# P1.net
KiCad netlist of a schematic drawn in Altium Designer
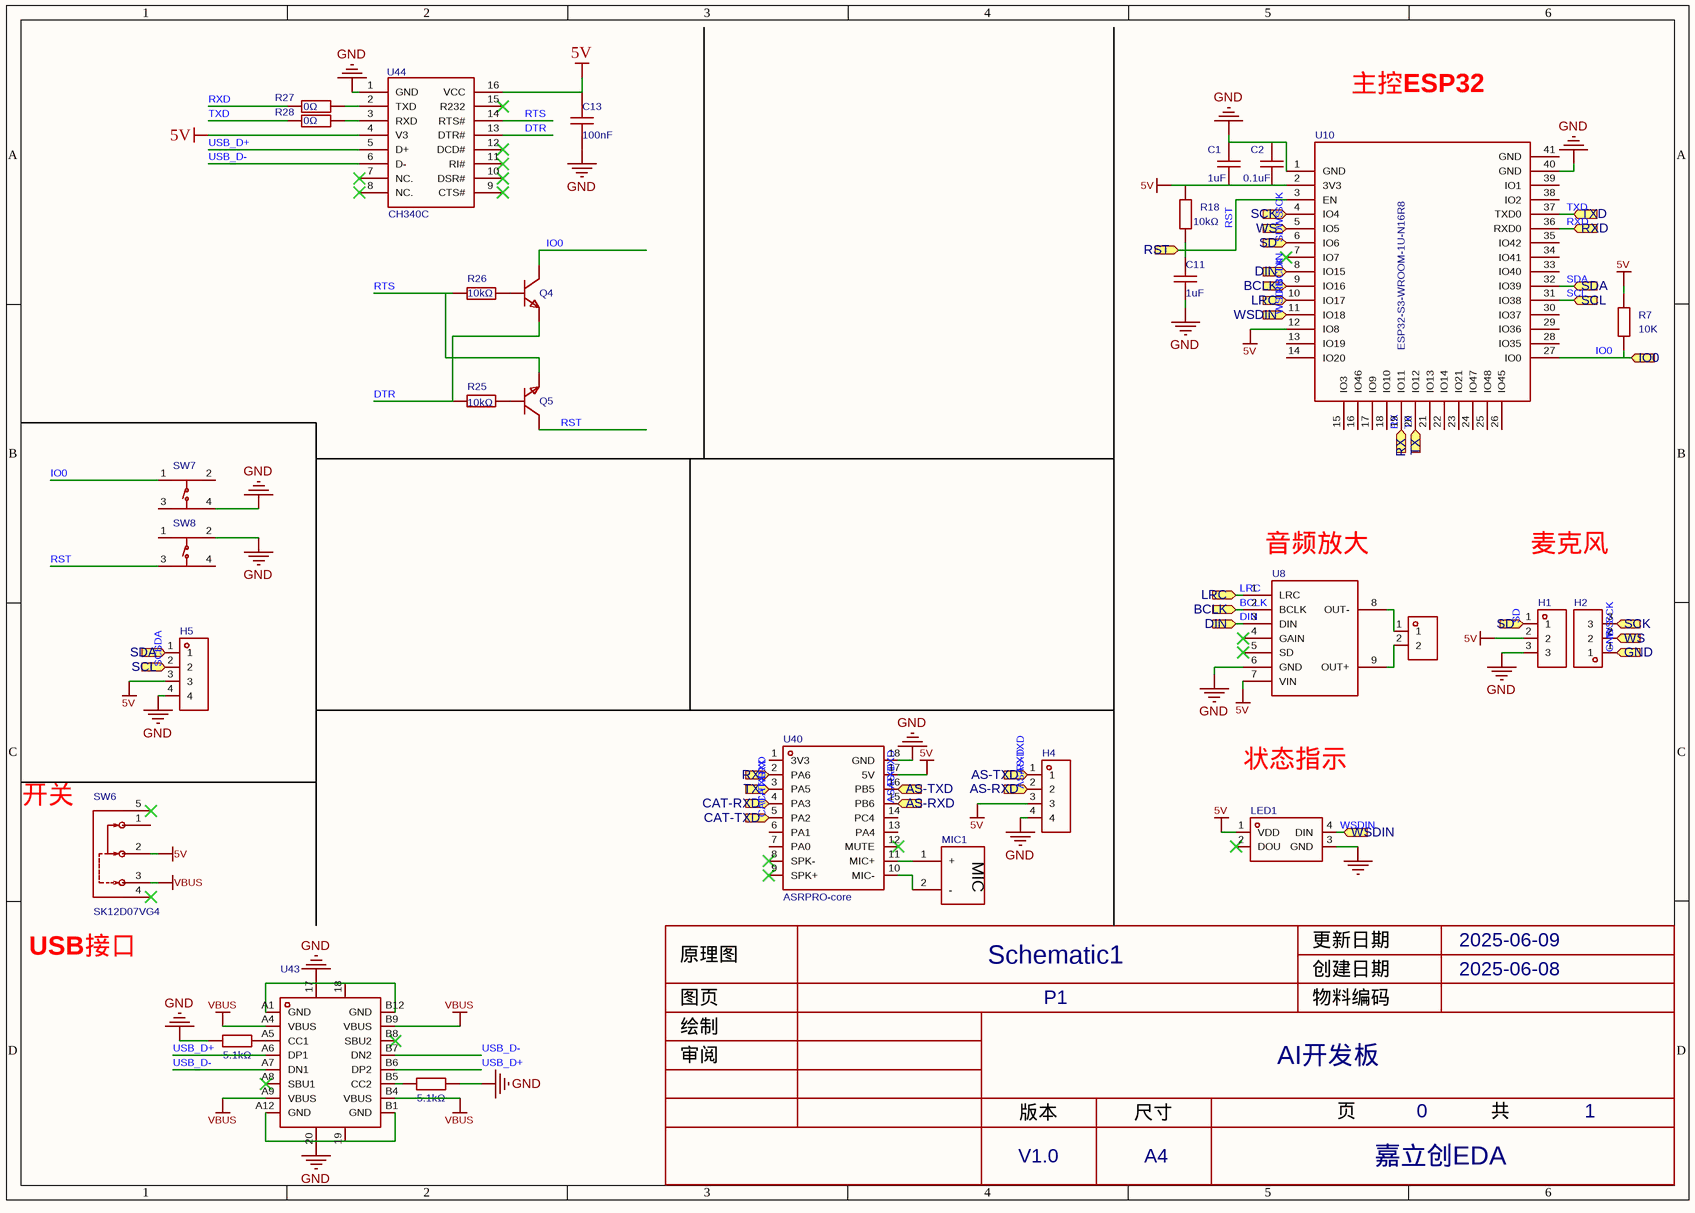
[diagram p0: P1.schdoc]

(export (version "E")
  (design (tool "Eeschema 10.0.6"))
  (components
    (comp (ref "C1")
      (value "1uF")
      (footprint "C0603")
      (description "容值:1uF;精度:±10%;额定电压:50V;材质(温度系数):X5R;")
      (fields (field (name "MANUFACTURER") "SAMSUNG(三星)") (field (name "MANUFACTURERPART") "CL10A105KB8NNNC"))
      (libsource (lib "altium-import") (part "root_1_CL10A105KB8NNNC_"))
    )
    (comp (ref "C2")
      (value "0.1uF")
      (footprint "C0603")
      (description "容值:1uF;精度:±10%;额定电压:50V;材质(温度系数):X5R;")
      (fields (field (name "MANUFACTURER") "SAMSUNG(三星)") (field (name "MANUFACTURERPART") "CL10A105KB8NNNC"))
      (libsource (lib "altium-import") (part "root_1_CL10A105KB8NNNC_"))
    )
    (comp (ref "C11")
      (value "1uF")
      (footprint "C0603")
      (description "容值:1uF;精度:±10%;额定电压:50V;材质(温度系数):X5R;")
      (fields (field (name "MANUFACTURER") "SAMSUNG(三星)") (field (name "MANUFACTURERPART") "CL10A105KB8NNNC"))
      (libsource (lib "altium-import") (part "root_1_CL10A105KB8NNNC_"))
    )
    (comp (ref "C13")
      (value "100nF")
      (footprint "C0603")
      (description "容值:100nF;精度:±10%;额定电压:50V;材质(温度系数):X7R;")
      (fields (field (name "MANUFACTURER") "YAGEO(国巨)") (field (name "MANUFACTURERPART") "CC0603KRX7R9BB104"))
      (libsource (lib "altium-import") (part "root_3_CC0603KRX7R9BB104_"))
    )
    (comp (ref "H1")
      (value "PZ254V-11-03P")
      (footprint "HDR-TH_3P-P2.54-V-M")
      (fields (field (name "MANUFACTURER") "XFCN(兴飞)"))
      (libsource (lib "altium-import") (part "root_0_PZ254V-11-03P_"))
    )
    (comp (ref "H2")
      (value "PZ254V-11-03P")
      (footprint "HDR-TH_3P-P2.54-V-M")
      (fields (field (name "MANUFACTURER") "XFCN(兴飞)"))
      (libsource (lib "altium-import") (part "root_2_PZ254V-11-03P_"))
    )
    (comp (ref "H3")
      (value "PZ254V-11-02P")
      (footprint "HDR-TH_2P-P2.54-V-M")
      (fields (field (name "MANUFACTURER") "XFCN(兴飞)"))
      (libsource (lib "altium-import") (part "root_0_PZ254V-11-02P_"))
    )
    (comp (ref "H4")
      (value "PZ254V-11-04P")
      (footprint "HDR-TH_4P-P2.54-V-M")
      (fields (field (name "MANUFACTURER") "XFCN(兴飞)"))
      (libsource (lib "altium-import") (part "root_0_PZ254V-11-04P_"))
    )
    (comp (ref "H5")
      (value "PZ254V-11-04P")
      (footprint "HDR-TH_4P-P2.54-V-M")
      (fields (field (name "MANUFACTURER") "XFCN(兴飞)"))
      (libsource (lib "altium-import") (part "root_0_PZ254V-11-04P_"))
    )
    (comp (ref "LED1")
      (value "XL-5050RGBC-WS2812B")
      (footprint "LED-SMD_4P-L5.0-W5.0-BL_XL-5050RGBC")
      (description "5050七彩幻彩透明贴片LED灯珠 5050 幻彩透明四脚 ws2812B 内置驱动IC")
      (fields (field (name "MANUFACTURER") "XINGLIGHT(成兴光)"))
      (libsource (lib "altium-import") (part "root_0_XL-5050RGBC-WS2812B_"))
    )
    (comp (ref "MIC1")
      (value "GMI6050P-36db")
      (footprint "MIC-TH_BD6.0-P1.90-D0.4-L-FD_GMI6050P-2CXXDB")
      (fields (field (name "MANUFACTURER") "INGHAi(赢海)"))
      (libsource (lib "altium-import") (part "root_3_GMI6050P-36db_"))
    )
    (comp (ref "Q4")
      (value "SS8050_C2150")
      (footprint "SOT-23-3_L2.9-W1.3-P1.90-LS2.4-BR")
      (description "晶体管类型:NPN;集电极电流(Ic):1.5A;集射极击穿电压(Vceo):25V;功率(Pd):300mW;直流电流增益(hFE@Ic,Vce):200@100mA,1V;")
      (fields (field (name "MANUFACTURER") "CJ(江苏长电/长晶)") (field (name "MANUFACTURERPART") "SS8050"))
      (libsource (lib "altium-import") (part "root_0_SS8050_C2150_"))
    )
    (comp (ref "Q5")
      (value "SS8050_C2150")
      (footprint "SOT-23-3_L2.9-W1.3-P1.90-LS2.4-BR")
      (description "晶体管类型:NPN;集电极电流(Ic):1.5A;集射极击穿电压(Vceo):25V;功率(Pd):300mW;直流电流增益(hFE@Ic,Vce):200@100mA,1V;")
      (fields (field (name "MANUFACTURER") "CJ(江苏长电/长晶)") (field (name "MANUFACTURERPART") "SS8050"))
      (libsource (lib "altium-import") (part "root_2_mirrored_SS8050_C2150_"))
    )
    (comp (ref "R6")
      (value "5.1kΩ")
      (footprint "R0603")
      (description "电阻类型:厚膜电阻;阻值:5.1kΩ;精度:±1%;功率:100mW;最大工作电压:75V;温度系数:±100ppm/℃;")
      (fields
        (field (name "MANUFACTURER PART") "0603WAF5101T5E")
        (field (name "MANUFACTURER") "UNI-ROYAL(厚声)")
      )
      (libsource (lib "altium-import") (part "root_0_0603WAF5101T5E_"))
    )
    (comp (ref "R7")
      (value "10K")
      (footprint "R0603")
      (description "电阻类型:厚膜电阻;阻值:10kΩ;精度:±1%;功率:100mW;")
      (fields
        (field (name "MANUFACTURER") "UNI-ROYAL(厚声)")
        (field (name "MANUFACTURERPART") "0603WAF1002T5E")
      )
      (libsource (lib "altium-import") (part "root_1_0603WAF1002T5E_"))
    )
    (comp (ref "R18")
      (value "10kΩ")
      (footprint "R0603")
      (description "电阻类型:厚膜电阻;阻值:10kΩ;精度:±1%;功率:100mW;")
      (fields
        (field (name "MANUFACTURER") "UNI-ROYAL(厚声)")
        (field (name "MANUFACTURERPART") "0603WAF1002T5E")
      )
      (libsource (lib "altium-import") (part "root_1_0603WAF1002T5E_"))
    )
    (comp (ref "R23")
      (value "5.1kΩ")
      (footprint "R0603")
      (description "电阻类型:厚膜电阻;阻值:5.1kΩ;精度:±1%;功率:100mW;最大工作电压:75V;温度系数:±100ppm/℃;")
      (fields
        (field (name "MANUFACTURER PART") "0603WAF5101T5E")
        (field (name "MANUFACTURER") "UNI-ROYAL(厚声)")
      )
      (libsource (lib "altium-import") (part "root_0_0603WAF5101T5E_"))
    )
    (comp (ref "R25")
      (value "10kΩ")
      (footprint "R0603")
      (description "电阻类型:厚膜电阻;阻值:10kΩ;精度:±1%;功率:100mW;最大工作电压:75V;温度系数:±100ppm/℃;")
      (fields
        (field (name "ALTIUM_VALUE") "10kΩ")
        (field (name "MANUFACTURER") "UNI-ROYAL(厚声)")
        (field (name "MANUFACTURERPART") "0603WAF1002T5E")
      )
      (libsource (lib "altium-import") (part "root_2_0603WAF1002T5E_"))
    )
    (comp (ref "R26")
      (value "10kΩ")
      (footprint "R0603")
      (description "电阻类型:厚膜电阻;阻值:10kΩ;精度:±1%;功率:100mW;最大工作电压:75V;温度系数:±100ppm/℃;")
      (fields
        (field (name "ALTIUM_VALUE") "10kΩ")
        (field (name "MANUFACTURER") "UNI-ROYAL(厚声)")
        (field (name "MANUFACTURERPART") "0603WAF1002T5E")
      )
      (libsource (lib "altium-import") (part "root_2_0603WAF1002T5E_"))
    )
    (comp (ref "R27")
      (value "0Ω")
      (footprint "R0603")
      (description "电阻类型:厚膜电阻;阻值:0Ω;精度:±1%;功率:100mW;")
      (fields
        (field (name "MANUFACTURER") "UNI-ROYAL(厚声)")
        (field (name "MANUFACTURERPART") "0603WAF0000T5E")
      )
      (libsource (lib "altium-import") (part "root_2_0603WAF0000T5E_"))
    )
    (comp (ref "R28")
      (value "0Ω")
      (footprint "R0603")
      (description "电阻类型:厚膜电阻;阻值:0Ω;精度:±1%;功率:100mW;")
      (fields
        (field (name "MANUFACTURER") "UNI-ROYAL(厚声)")
        (field (name "MANUFACTURERPART") "0603WAF0000T5E")
      )
      (libsource (lib "altium-import") (part "root_2_0603WAF0000T5E_"))
    )
    (comp (ref "SW6")
      (value "SK12D07VG4")
      (footprint "SW-TH_SK12D07VG4")
      (description "电路结构:单刀双掷;安装方式:-;额定电流(DC):500mA;额定电压(DC):50V;额定电流(AC):-;额定电压(AC):-;机械寿命:5千次;")
      (fields (field (name "MANUFACTURER") "SHOU HAN(首韩)"))
      (libsource (lib "altium-import") (part "root_3_mirrored_SK12D07VG4_"))
    )
    (comp (ref "SW7")
      (value "TS-KG89S-AT25F")
      (footprint "SW-SMD_4P-L4.2-W3.3-P2.15-LS5.1")
      (description "触点电流:50mA;额定电压(DC):12V;绝缘电阻:100MΩ;电路结构:单刀单掷;安装方式:立贴;作用力:250gf@±50gf;机械寿命:10万次;带支架:否;")
      (fields (field (name "MANUFACTURER") "HANBO(汉博)"))
      (libsource (lib "altium-import") (part "root_0_TS-KG89S-AT25F_"))
    )
    (comp (ref "SW8")
      (value "TS-KG89S-AT25F")
      (footprint "SW-SMD_4P-L4.2-W3.3-P2.15-LS5.1")
      (description "触点电流:50mA;额定电压(DC):12V;绝缘电阻:100MΩ;电路结构:单刀单掷;安装方式:立贴;作用力:250gf@±50gf;机械寿命:10万次;带支架:否;")
      (fields (field (name "MANUFACTURER") "HANBO(汉博)"))
      (libsource (lib "altium-import") (part "root_0_TS-KG89S-AT25F_"))
    )
    (comp (ref "U8")
      (value "~")
      (footprint "MAX98357moudle")
      (libsource (lib "altium-import") (part "root_3_MAX98357模块_"))
    )
    (comp (ref "U10")
      (value "ESP32-S3-WROOM-1U-N16R8")
      (footprint "WIRELM-SMD_ESP32-S3-WROOM-1U")
      (fields (field (name "MANUFACTURER") "ESPRESSIF(乐鑫)"))
      (libsource (lib "altium-import") (part "root_0_ESP32-S3-WROOM-1U-N16R8_"))
    )
    (comp (ref "U40")
      (value "ASRPRO-core")
      (footprint "COMM-SMD_ASRPRO-CORE-V1.1")
      (libsource (lib "altium-import") (part "root_0_ASRPRO-core_C9900107962_"))
    )
    (comp (ref "U43")
      (value "24018-UCAF001-A")
      (footprint "TYPE-C-USB-SMD_CF003")
      (description "TYPE C 16P母座加高1.0 H=4.25无弹")
      (fields (field (name "MANUFACTURER") "MINTRON(明硕)"))
      (libsource (lib "altium-import") (part "root_0_24018-UCAF001-A_"))
    )
    (comp (ref "U44")
      (value "CH340C")
      (footprint "SOP-16_L10.0-W3.9-P1.27-LS6.0-BL")
      (description "类型:Transceiver;协议类别:USB 2.0;驱动器/接收器数:-;数据速率:2Mbps;")
      (fields (field (name "DEVICE") "CH340C") (field (name "MANUFACTURER") "WCH(南京沁恒)"))
      (libsource (lib "altium-import") (part "root_0_CH340C_"))
    )
  )
  (nets
    (net (code "1") (name "/AS-RXD") (class "Default")
      (node (ref "H4") (pin "2") (pinfunction "2_2") (pintype "passive"))
      (node (ref "U40") (pin "15") (pinfunction "PB6_15") (pintype "passive"))
    )
    (net (code "2") (name "/AS-TXD") (class "Default")
      (node (ref "H4") (pin "1") (pinfunction "1_1") (pintype "passive"))
      (node (ref "U40") (pin "16") (pinfunction "PB5_16") (pintype "passive"))
    )
    (net (code "3") (name "/BCLK") (class "Default")
      (node (ref "U10") (pin "9") (pinfunction "IO16_9") (pintype "passive"))
      (node (ref "U8") (pin "2") (pinfunction "BCLK_2") (pintype "passive"))
    )
    (net (code "4") (name "/CAT-RXD") (class "Default")
      (node (ref "U40") (pin "4") (pinfunction "PA3_4") (pintype "passive"))
    )
    (net (code "5") (name "/CAT-TXD") (class "Default")
      (node (ref "U40") (pin "5") (pinfunction "PA2_5") (pintype "passive"))
    )
    (net (code "6") (name "/DIN") (class "Default")
      (node (ref "U10") (pin "8") (pinfunction "IO15_8") (pintype "passive"))
      (node (ref "U8") (pin "3") (pinfunction "DIN_3") (pintype "passive"))
    )
    (net (code "7") (name "/DTR") (class "Default")
      (node (ref "Q4") (pin "2") (pinfunction "E_2") (pintype "passive"))
      (node (ref "R25") (pin "2") (pinfunction "2_2") (pintype "passive"))
      (node (ref "U44") (pin "13") (pinfunction "DTR#_13") (pintype "passive"))
    )
    (net (code "8") (name "/IO0") (class "Default")
      (node (ref "Q4") (pin "3") (pinfunction "C_3") (pintype "passive"))
      (node (ref "R7") (pin "1") (pinfunction "1_1") (pintype "passive"))
      (node (ref "SW7") (pin "1") (pinfunction "1_1") (pintype "passive"))
      (node (ref "U10") (pin "27") (pinfunction "IO0_27") (pintype "passive"))
    )
    (net (code "9") (name "/LRC") (class "Default")
      (node (ref "U10") (pin "10") (pinfunction "IO17_10") (pintype "passive"))
      (node (ref "U8") (pin "1") (pinfunction "LRC_1") (pintype "passive"))
    )
    (net (code "10") (name "/RST") (class "Default")
      (node (ref "C11") (pin "2") (pinfunction "2_2") (pintype "passive"))
      (node (ref "Q5") (pin "3") (pinfunction "C_3") (pintype "passive"))
      (node (ref "R18") (pin "1") (pinfunction "1_1") (pintype "passive"))
      (node (ref "SW8") (pin "3") (pinfunction "3_3") (pintype "passive"))
      (node (ref "U10") (pin "3") (pinfunction "EN_3") (pintype "passive"))
    )
    (net (code "11") (name "/RTS") (class "Default")
      (node (ref "Q5") (pin "2") (pinfunction "E_2") (pintype "passive"))
      (node (ref "R26") (pin "2") (pinfunction "2_2") (pintype "passive"))
      (node (ref "U44") (pin "14") (pinfunction "RTS#_14") (pintype "passive"))
    )
    (net (code "12") (name "/RX") (class "Default")
      (node (ref "U10") (pin "19") (pinfunction "IO11_19") (pintype "passive"))
      (node (ref "U40") (pin "2") (pinfunction "PA6_2") (pintype "passive"))
    )
    (net (code "13") (name "/RXD") (class "Default")
      (node (ref "R27") (pin "2") (pinfunction "2_2") (pintype "passive"))
      (node (ref "U10") (pin "36") (pinfunction "RXD0_36") (pintype "passive"))
    )
    (net (code "14") (name "/SCK") (class "Default")
      (node (ref "H2") (pin "3") (pinfunction "3_3") (pintype "passive"))
      (node (ref "U10") (pin "4") (pinfunction "IO4_4") (pintype "passive"))
    )
    (net (code "15") (name "/SCL") (class "Default")
      (node (ref "H5") (pin "2") (pinfunction "2_2") (pintype "passive"))
      (node (ref "U10") (pin "31") (pinfunction "IO38_31") (pintype "passive"))
    )
    (net (code "16") (name "/SD") (class "Default")
      (node (ref "H1") (pin "1") (pinfunction "1_1") (pintype "passive"))
      (node (ref "U10") (pin "6") (pinfunction "IO6_6") (pintype "passive"))
    )
    (net (code "17") (name "/SDA") (class "Default")
      (node (ref "H5") (pin "1") (pinfunction "1_1") (pintype "passive"))
      (node (ref "U10") (pin "32") (pinfunction "IO39_32") (pintype "passive"))
    )
    (net (code "18") (name "/TX") (class "Default")
      (node (ref "U10") (pin "20") (pinfunction "IO12_20") (pintype "passive"))
      (node (ref "U40") (pin "3") (pinfunction "PA5_3") (pintype "passive"))
    )
    (net (code "19") (name "/TXD") (class "Default")
      (node (ref "R28") (pin "2") (pinfunction "2_2") (pintype "passive"))
      (node (ref "U10") (pin "37") (pinfunction "TXD0_37") (pintype "passive"))
    )
    (net (code "20") (name "/USB_D+") (class "Default")
      (node (ref "U43") (pin "A6") (pinfunction "DP1_A6") (pintype "passive"))
      (node (ref "U43") (pin "B6") (pinfunction "DP2_B6") (pintype "passive"))
      (node (ref "U44") (pin "5") (pinfunction "D+_5") (pintype "passive"))
    )
    (net (code "21") (name "/USB_D-") (class "Default")
      (node (ref "U43") (pin "A7") (pinfunction "DN1_A7") (pintype "passive"))
      (node (ref "U43") (pin "B7") (pinfunction "DN2_B7") (pintype "passive"))
      (node (ref "U44") (pin "6") (pinfunction "D-_6") (pintype "passive"))
    )
    (net (code "22") (name "/WS") (class "Default")
      (node (ref "H2") (pin "2") (pinfunction "2_2") (pintype "passive"))
      (node (ref "U10") (pin "5") (pinfunction "IO5_5") (pintype "passive"))
    )
    (net (code "23") (name "/WSDIN") (class "Default")
      (node (ref "LED1") (pin "4") (pinfunction "DIN_4") (pintype "passive"))
      (node (ref "U10") (pin "11") (pinfunction "IO18_11") (pintype "passive"))
    )
    (net (code "24") (name "5V") (class "Default")
      (node (ref "C1") (pin "1") (pinfunction "1_1") (pintype "passive"))
      (node (ref "C13") (pin "1") (pinfunction "1_1") (pintype "passive"))
      (node (ref "C2") (pin "1") (pinfunction "1_1") (pintype "passive"))
      (node (ref "H1") (pin "2") (pinfunction "2_2") (pintype "passive"))
      (node (ref "H4") (pin "3") (pinfunction "3_3") (pintype "passive"))
      (node (ref "H5") (pin "3") (pinfunction "3_3") (pintype "passive"))
      (node (ref "LED1") (pin "1") (pinfunction "VDD_1") (pintype "passive"))
      (node (ref "R18") (pin "2") (pinfunction "2_2") (pintype "passive"))
      (node (ref "R7") (pin "2") (pinfunction "2_2") (pintype "passive"))
      (node (ref "SW6") (pin "2") (pinfunction "2_2") (pintype "passive"))
      (node (ref "U10") (pin "12") (pinfunction "IO8_12") (pintype "passive"))
      (node (ref "U10") (pin "2") (pinfunction "3V3_2") (pintype "passive"))
      (node (ref "U40") (pin "17") (pinfunction "5V_17") (pintype "passive"))
      (node (ref "U44") (pin "16") (pinfunction "VCC_16") (pintype "passive"))
      (node (ref "U44") (pin "4") (pinfunction "V3_4") (pintype "passive"))
      (node (ref "U8") (pin "7") (pinfunction "VIN_7") (pintype "passive"))
    )
    (net (code "25") (name "GND") (class "Default")
      (node (ref "C1") (pin "2") (pinfunction "2_2") (pintype "passive"))
      (node (ref "C11") (pin "1") (pinfunction "1_1") (pintype "passive"))
      (node (ref "C13") (pin "2") (pinfunction "2_2") (pintype "passive"))
      (node (ref "C2") (pin "2") (pinfunction "2_2") (pintype "passive"))
      (node (ref "H1") (pin "3") (pinfunction "3_3") (pintype "passive"))
      (node (ref "H2") (pin "1") (pinfunction "1_1") (pintype "passive"))
      (node (ref "H4") (pin "4") (pinfunction "4_4") (pintype "passive"))
      (node (ref "H5") (pin "4") (pinfunction "4_4") (pintype "passive"))
      (node (ref "LED1") (pin "3") (pinfunction "GND_3") (pintype "passive"))
      (node (ref "R23") (pin "1") (pinfunction "1_1") (pintype "passive"))
      (node (ref "R6") (pin "2") (pinfunction "2_2") (pintype "passive"))
      (node (ref "SW7") (pin "4") (pinfunction "4_4") (pintype "passive"))
      (node (ref "SW8") (pin "2") (pinfunction "2_2") (pintype "passive"))
      (node (ref "U10") (pin "1") (pinfunction "GND_1") (pintype "passive"))
      (node (ref "U10") (pin "40") (pinfunction "GND_40") (pintype "passive"))
      (node (ref "U40") (pin "18") (pinfunction "GND_18") (pintype "passive"))
      (node (ref "U43") (pin "17") (pinfunction "17_17") (pintype "passive"))
      (node (ref "U43") (pin "18") (pinfunction "18_18") (pintype "passive"))
      (node (ref "U43") (pin "19") (pinfunction "19_19") (pintype "passive"))
      (node (ref "U43") (pin "20") (pinfunction "20_20") (pintype "passive"))
      (node (ref "U43") (pin "A1") (pinfunction "GND_A1") (pintype "passive"))
      (node (ref "U43") (pin "A12") (pinfunction "GND_A12") (pintype "passive"))
      (node (ref "U43") (pin "B1") (pinfunction "GND_B1") (pintype "passive"))
      (node (ref "U43") (pin "B12") (pinfunction "GND_B12") (pintype "passive"))
      (node (ref "U44") (pin "1") (pinfunction "GND_1") (pintype "passive"))
      (node (ref "U8") (pin "6") (pinfunction "GND_6") (pintype "passive"))
    )
    (net (code "26") (name "Net-(MIC1-+)") (class "Default")
      (node (ref "MIC1") (pin "1") (pinfunction "+_1") (pintype "passive"))
      (node (ref "U40") (pin "11") (pinfunction "MIC+_11") (pintype "passive"))
    )
    (net (code "27") (name "Net-(MIC1--)") (class "Default")
      (node (ref "MIC1") (pin "2") (pinfunction "-_2") (pintype "passive"))
      (node (ref "U40") (pin "10") (pinfunction "MIC-_10") (pintype "passive"))
    )
    (net (code "28") (name "Net-(Q4-B)") (class "Default")
      (node (ref "Q4") (pin "1") (pinfunction "B_1") (pintype "passive"))
      (node (ref "R26") (pin "1") (pinfunction "1_1") (pintype "passive"))
    )
    (net (code "29") (name "Net-(Q5-B)") (class "Default")
      (node (ref "Q5") (pin "1") (pinfunction "B_1") (pintype "passive"))
      (node (ref "R25") (pin "1") (pinfunction "1_1") (pintype "passive"))
    )
    (net (code "30") (name "Net-(U8-OUT+)") (class "Default")
      (node (ref "H3") (pin "2") (pinfunction "2_2") (pintype "passive"))
      (node (ref "U8") (pin "9") (pinfunction "OUT+_9") (pintype "passive"))
    )
    (net (code "31") (name "Net-(U8-OUT-)") (class "Default")
      (node (ref "H3") (pin "1") (pinfunction "1_1") (pintype "passive"))
      (node (ref "U8") (pin "8") (pinfunction "OUT-_8") (pintype "passive"))
    )
    (net (code "32") (name "Net-(U43-CC1)") (class "Default")
      (node (ref "R23") (pin "2") (pinfunction "2_2") (pintype "passive"))
      (node (ref "U43") (pin "A5") (pinfunction "CC1_A5") (pintype "passive"))
    )
    (net (code "33") (name "Net-(U43-CC2)") (class "Default")
      (node (ref "R6") (pin "1") (pinfunction "1_1") (pintype "passive"))
      (node (ref "U43") (pin "B5") (pinfunction "CC2_B5") (pintype "passive"))
    )
    (net (code "34") (name "Net-(U44-RXD)") (class "Default")
      (node (ref "R28") (pin "1") (pinfunction "1_1") (pintype "passive"))
      (node (ref "U44") (pin "3") (pinfunction "RXD_3") (pintype "passive"))
    )
    (net (code "35") (name "Net-(U44-TXD)") (class "Default")
      (node (ref "R27") (pin "1") (pinfunction "1_1") (pintype "passive"))
      (node (ref "U44") (pin "2") (pinfunction "TXD_2") (pintype "passive"))
    )
    (net (code "36") (name "VBUS") (class "Default")
      (node (ref "SW6") (pin "3") (pinfunction "3_3") (pintype "passive"))
      (node (ref "U43") (pin "A4") (pinfunction "VBUS_A4") (pintype "passive"))
      (node (ref "U43") (pin "A9") (pinfunction "VBUS_A9") (pintype "passive"))
      (node (ref "U43") (pin "B4") (pinfunction "VBUS_B4") (pintype "passive"))
      (node (ref "U43") (pin "B9") (pinfunction "VBUS_B9") (pintype "passive"))
    )
    (net (code "37") (name "unconnected-(LED1-DOU-Pad2)") (class "Default")
      (node (ref "LED1") (pin "2") (pinfunction "DOU_2") (pintype "passive+no_connect"))
    )
    (net (code "38") (name "unconnected-(SW6-Pad1)") (class "Default")
      (node (ref "SW6") (pin "1") (pinfunction "1_1") (pintype "passive"))
    )
    (net (code "39") (name "unconnected-(SW6-Pad4)") (class "Default")
      (node (ref "SW6") (pin "4") (pinfunction "4_4") (pintype "passive+no_connect"))
    )
    (net (code "40") (name "unconnected-(SW6-Pad5)") (class "Default")
      (node (ref "SW6") (pin "5") (pinfunction "5_5") (pintype "passive+no_connect"))
    )
    (net (code "41") (name "unconnected-(SW7-Pad2)") (class "Default")
      (node (ref "SW7") (pin "2") (pinfunction "2_2") (pintype "passive"))
    )
    (net (code "42") (name "unconnected-(SW7-Pad3)") (class "Default")
      (node (ref "SW7") (pin "3") (pinfunction "3_3") (pintype "passive"))
    )
    (net (code "43") (name "unconnected-(SW8-Pad1)") (class "Default")
      (node (ref "SW8") (pin "1") (pinfunction "1_1") (pintype "passive"))
    )
    (net (code "44") (name "unconnected-(SW8-Pad4)") (class "Default")
      (node (ref "SW8") (pin "4") (pinfunction "4_4") (pintype "passive"))
    )
    (net (code "45") (name "unconnected-(U8-GAIN-Pad4)") (class "Default")
      (node (ref "U8") (pin "4") (pinfunction "GAIN_4") (pintype "passive+no_connect"))
    )
    (net (code "46") (name "unconnected-(U8-SD-Pad5)") (class "Default")
      (node (ref "U8") (pin "5") (pinfunction "SD_5") (pintype "passive+no_connect"))
    )
    (net (code "47") (name "unconnected-(U10-GND-Pad41)") (class "Default")
      (node (ref "U10") (pin "41") (pinfunction "GND_41") (pintype "passive"))
    )
    (net (code "48") (name "unconnected-(U10-IO1-Pad39)") (class "Default")
      (node (ref "U10") (pin "39") (pinfunction "IO1_39") (pintype "passive"))
    )
    (net (code "49") (name "unconnected-(U10-IO2-Pad38)") (class "Default")
      (node (ref "U10") (pin "38") (pinfunction "IO2_38") (pintype "passive"))
    )
    (net (code "50") (name "unconnected-(U10-IO3-Pad15)") (class "Default")
      (node (ref "U10") (pin "15") (pinfunction "IO3_15") (pintype "passive"))
    )
    (net (code "51") (name "unconnected-(U10-IO7-Pad7)") (class "Default")
      (node (ref "U10") (pin "7") (pinfunction "IO7_7") (pintype "passive+no_connect"))
    )
    (net (code "52") (name "unconnected-(U10-IO9-Pad17)") (class "Default")
      (node (ref "U10") (pin "17") (pinfunction "IO9_17") (pintype "passive"))
    )
    (net (code "53") (name "unconnected-(U10-IO10-Pad18)") (class "Default")
      (node (ref "U10") (pin "18") (pinfunction "IO10_18") (pintype "passive"))
    )
    (net (code "54") (name "unconnected-(U10-IO13-Pad21)") (class "Default")
      (node (ref "U10") (pin "21") (pinfunction "IO13_21") (pintype "passive"))
    )
    (net (code "55") (name "unconnected-(U10-IO14-Pad22)") (class "Default")
      (node (ref "U10") (pin "22") (pinfunction "IO14_22") (pintype "passive"))
    )
    (net (code "56") (name "unconnected-(U10-IO19-Pad13)") (class "Default")
      (node (ref "U10") (pin "13") (pinfunction "IO19_13") (pintype "passive"))
    )
    (net (code "57") (name "unconnected-(U10-IO20-Pad14)") (class "Default")
      (node (ref "U10") (pin "14") (pinfunction "IO20_14") (pintype "passive"))
    )
    (net (code "58") (name "unconnected-(U10-IO21-Pad23)") (class "Default")
      (node (ref "U10") (pin "23") (pinfunction "IO21_23") (pintype "passive"))
    )
    (net (code "59") (name "unconnected-(U10-IO35-Pad28)") (class "Default")
      (node (ref "U10") (pin "28") (pinfunction "IO35_28") (pintype "passive"))
    )
    (net (code "60") (name "unconnected-(U10-IO36-Pad29)") (class "Default")
      (node (ref "U10") (pin "29") (pinfunction "IO36_29") (pintype "passive"))
    )
    (net (code "61") (name "unconnected-(U10-IO37-Pad30)") (class "Default")
      (node (ref "U10") (pin "30") (pinfunction "IO37_30") (pintype "passive"))
    )
    (net (code "62") (name "unconnected-(U10-IO40-Pad33)") (class "Default")
      (node (ref "U10") (pin "33") (pinfunction "IO40_33") (pintype "passive"))
    )
    (net (code "63") (name "unconnected-(U10-IO41-Pad34)") (class "Default")
      (node (ref "U10") (pin "34") (pinfunction "IO41_34") (pintype "passive"))
    )
    (net (code "64") (name "unconnected-(U10-IO42-Pad35)") (class "Default")
      (node (ref "U10") (pin "35") (pinfunction "IO42_35") (pintype "passive"))
    )
    (net (code "65") (name "unconnected-(U10-IO45-Pad26)") (class "Default")
      (node (ref "U10") (pin "26") (pinfunction "IO45_26") (pintype "passive"))
    )
    (net (code "66") (name "unconnected-(U10-IO46-Pad16)") (class "Default")
      (node (ref "U10") (pin "16") (pinfunction "IO46_16") (pintype "passive"))
    )
    (net (code "67") (name "unconnected-(U10-IO47-Pad24)") (class "Default")
      (node (ref "U10") (pin "24") (pinfunction "IO47_24") (pintype "passive"))
    )
    (net (code "68") (name "unconnected-(U10-IO48-Pad25)") (class "Default")
      (node (ref "U10") (pin "25") (pinfunction "IO48_25") (pintype "passive"))
    )
    (net (code "69") (name "unconnected-(U40-3V3-Pad1)") (class "Default")
      (node (ref "U40") (pin "1") (pinfunction "3V3_1") (pintype "passive"))
    )
    (net (code "70") (name "unconnected-(U40-MUTE-Pad12)") (class "Default")
      (node (ref "U40") (pin "12") (pinfunction "MUTE_12") (pintype "passive+no_connect"))
    )
    (net (code "71") (name "unconnected-(U40-PA0-Pad7)") (class "Default")
      (node (ref "U40") (pin "7") (pinfunction "PA0_7") (pintype "passive"))
    )
    (net (code "72") (name "unconnected-(U40-PA1-Pad6)") (class "Default")
      (node (ref "U40") (pin "6") (pinfunction "PA1_6") (pintype "passive"))
    )
    (net (code "73") (name "unconnected-(U40-PA4-Pad13)") (class "Default")
      (node (ref "U40") (pin "13") (pinfunction "PA4_13") (pintype "passive"))
    )
    (net (code "74") (name "unconnected-(U40-PC4-Pad14)") (class "Default")
      (node (ref "U40") (pin "14") (pinfunction "PC4_14") (pintype "passive"))
    )
    (net (code "75") (name "unconnected-(U40-SPK+-Pad9)") (class "Default")
      (node (ref "U40") (pin "9") (pinfunction "SPK+_9") (pintype "passive+no_connect"))
    )
    (net (code "76") (name "unconnected-(U40-SPK--Pad8)") (class "Default")
      (node (ref "U40") (pin "8") (pinfunction "SPK-_8") (pintype "passive+no_connect"))
    )
    (net (code "77") (name "unconnected-(U43-SBU1-PadA8)") (class "Default")
      (node (ref "U43") (pin "A8") (pinfunction "SBU1_A8") (pintype "passive+no_connect"))
    )
    (net (code "78") (name "unconnected-(U43-SBU2-PadB8)") (class "Default")
      (node (ref "U43") (pin "B8") (pinfunction "SBU2_B8") (pintype "passive+no_connect"))
    )
    (net (code "79") (name "unconnected-(U44-CTS#-Pad9)") (class "Default")
      (node (ref "U44") (pin "9") (pinfunction "CTS#_9") (pintype "passive+no_connect"))
    )
    (net (code "80") (name "unconnected-(U44-DCD#-Pad12)") (class "Default")
      (node (ref "U44") (pin "12") (pinfunction "DCD#_12") (pintype "passive+no_connect"))
    )
    (net (code "81") (name "unconnected-(U44-DSR#-Pad10)") (class "Default")
      (node (ref "U44") (pin "10") (pinfunction "DSR#_10") (pintype "passive+no_connect"))
    )
    (net (code "82") (name "unconnected-(U44-NC.-Pad7)") (class "Default")
      (node (ref "U44") (pin "7") (pinfunction "NC._7") (pintype "passive+no_connect"))
    )
    (net (code "83") (name "unconnected-(U44-NC.-Pad8)") (class "Default")
      (node (ref "U44") (pin "8") (pinfunction "NC._8") (pintype "passive+no_connect"))
    )
    (net (code "84") (name "unconnected-(U44-R232-Pad15)") (class "Default")
      (node (ref "U44") (pin "15") (pinfunction "R232_15") (pintype "passive+no_connect"))
    )
    (net (code "85") (name "unconnected-(U44-RI#-Pad11)") (class "Default")
      (node (ref "U44") (pin "11") (pinfunction "RI#_11") (pintype "passive+no_connect"))
    )
  )
)
